# RoverPCB_version_4_2.net
KiCad netlist of a schematic drawn in EAGLE
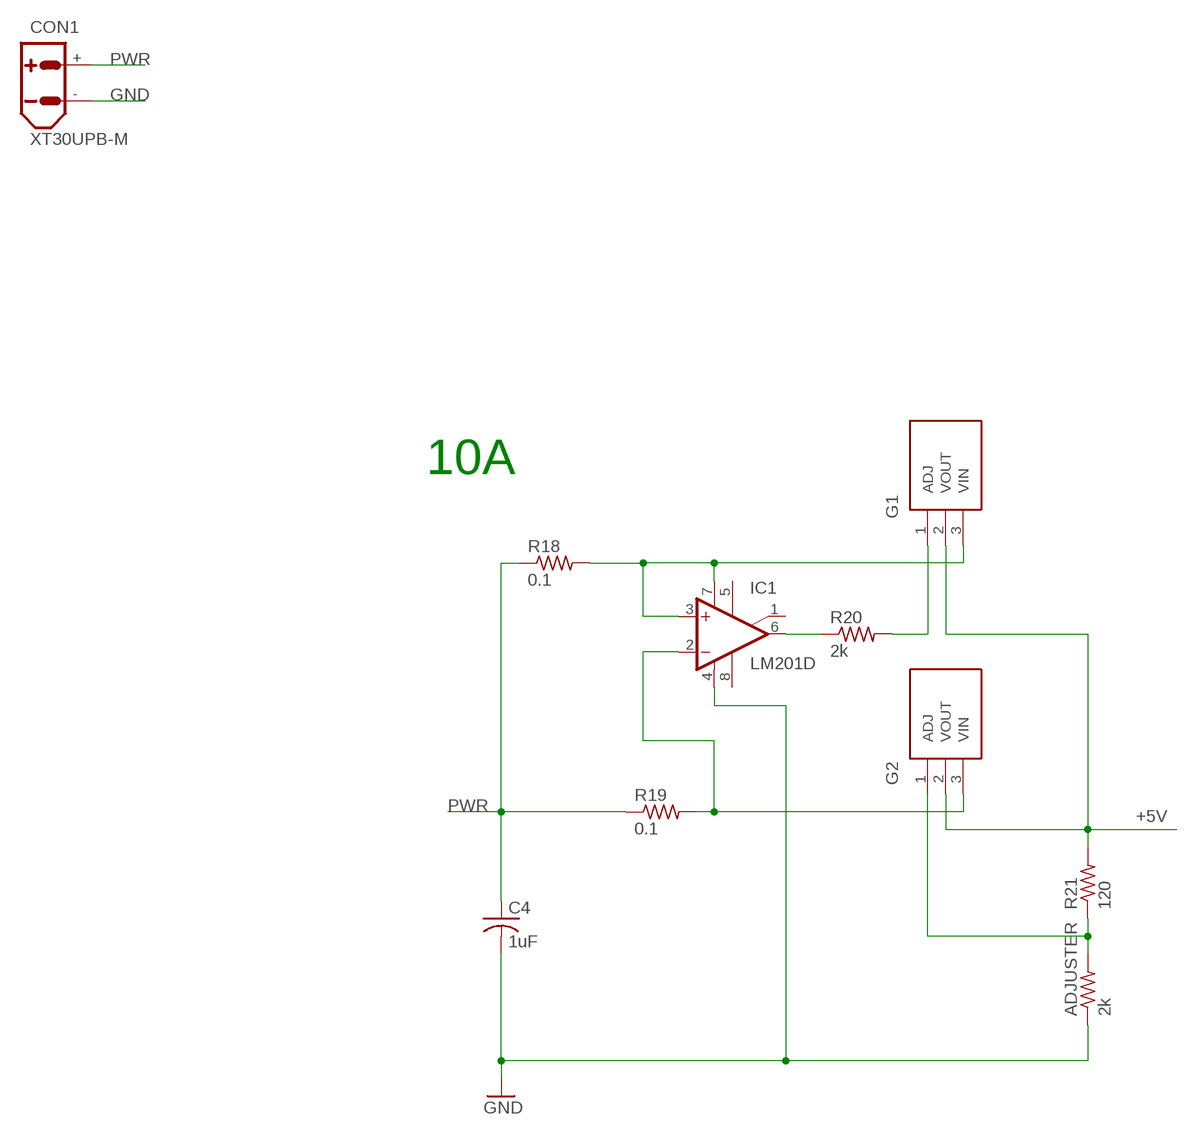
[diagram p0: schematic, sheet 1]
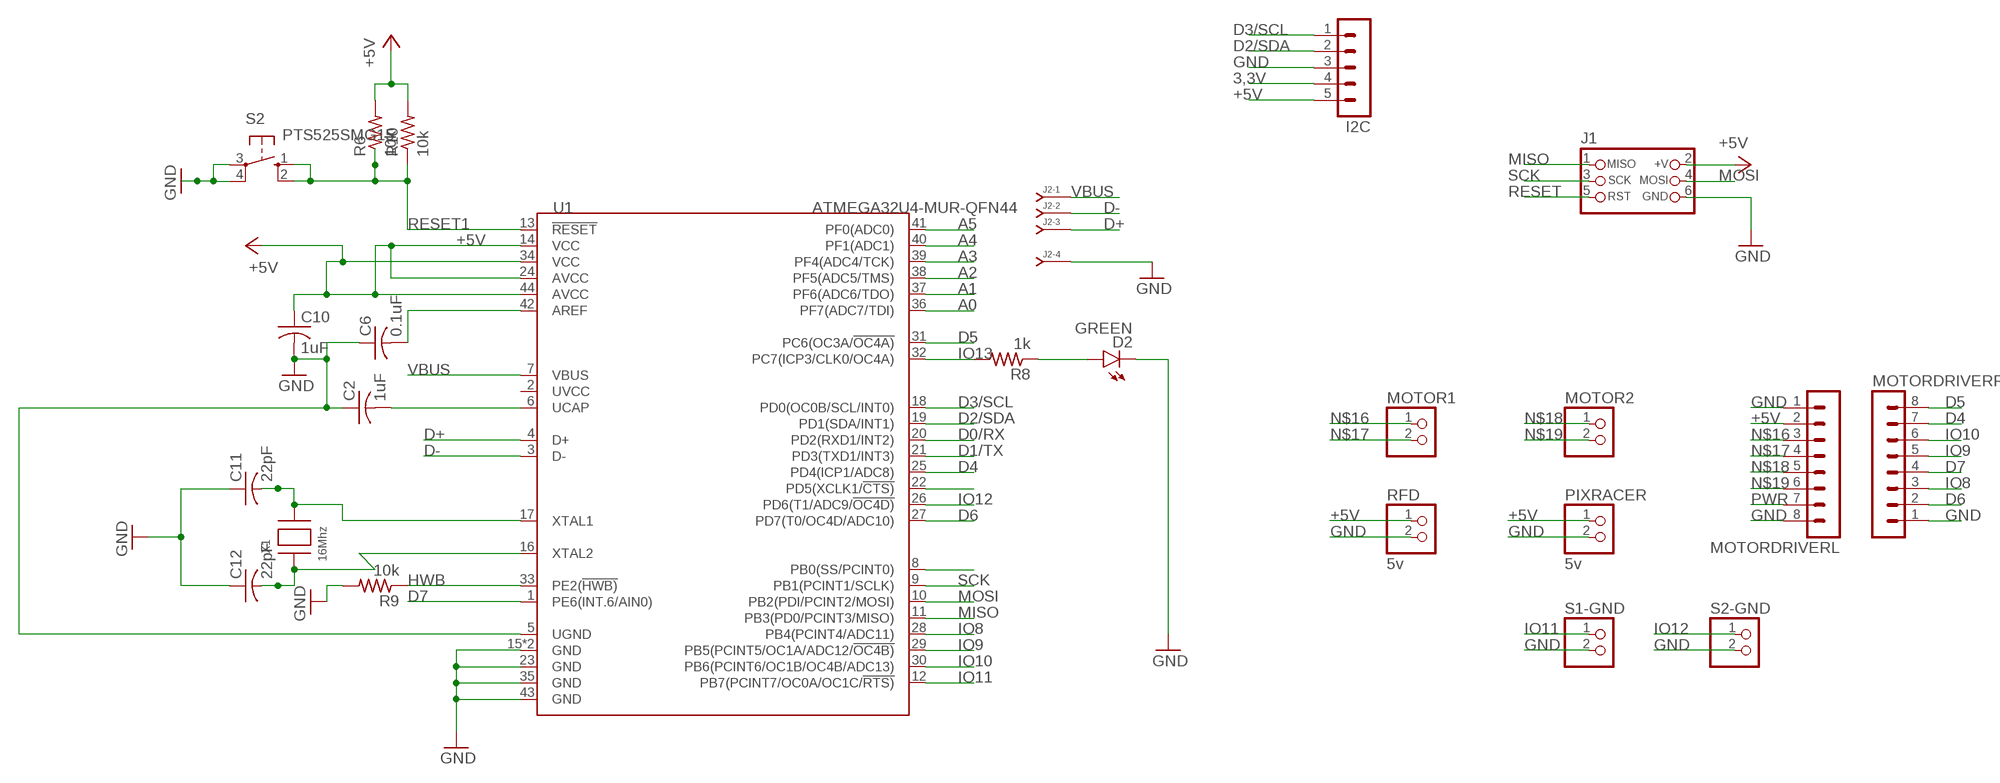
[diagram p1: schematic, sheet 2]

(export (version "E")
  (design (tool "Eeschema 10.0.6"))
  (components
    (comp (ref "ADJUSTER")
      (value "2k")
      (footprint "eagle-import:0204_5")
      (libsource (lib "eagle-import") (part "R-US_0204/5"))
    )
    (comp (ref "C4")
      (value "1uF")
      (footprint "eagle-import:C0402K")
      (libsource (lib "eagle-import") (part "C-USC0402K"))
    )
    (comp (ref "CON1")
      (value "XT30UPB-M")
      (footprint "eagle-import:XT30UPB-M")
      (libsource (lib "eagle-import") (part "XT30UPB-M"))
    )
    (comp (ref "IC1")
      (value "LM201D")
      (footprint "eagle-import:SO08")
      (libsource (lib "eagle-import") (part "LM201D"))
    )
    (comp (ref "IC11")
      (value "G1")
      (footprint "eagle-import:TO254P470X1028X1955-3P")
      (fields
        (field (name "ARROW_PART_NUMBER") "LM338T/NOPB")
        (field (name "MOUSER_PART_NUMBER") "926-LM338T/NOPB")
      )
      (libsource (lib "eagle-import") (part "LM338T_NOPB"))
    )
    (comp (ref "IC12")
      (value "G2")
      (footprint "eagle-import:TO254P470X1028X1955-3P")
      (fields
        (field (name "ARROW_PART_NUMBER") "LM338T/NOPB")
        (field (name "MOUSER_PART_NUMBER") "926-LM338T/NOPB")
      )
      (libsource (lib "eagle-import") (part "LM338T_NOPB"))
    )
    (comp (ref "R18")
      (value "0.1")
      (footprint "eagle-import:M1206")
      (libsource (lib "eagle-import") (part "R-US_M1206"))
    )
    (comp (ref "R19")
      (value "0.1")
      (footprint "eagle-import:M1206")
      (libsource (lib "eagle-import") (part "R-US_M1206"))
    )
    (comp (ref "R20")
      (value "2k")
      (footprint "eagle-import:R0805")
      (libsource (lib "eagle-import") (part "R-US_R0805"))
    )
    (comp (ref "R21")
      (value "120")
      (footprint "eagle-import:R0805")
      (libsource (lib "eagle-import") (part "R-US_R0805"))
    )
    (comp (ref "C2")
      (value "1uF")
      (footprint "eagle-import:C0805")
      (libsource (lib "eagle-import") (part "C-USC0805"))
    )
    (comp (ref "C6")
      (value "0.1uF")
      (footprint "eagle-import:C0805")
      (libsource (lib "eagle-import") (part "C-USC0805"))
    )
    (comp (ref "C10")
      (value "1uF")
      (footprint "eagle-import:C0805")
      (libsource (lib "eagle-import") (part "C-USC0805"))
    )
    (comp (ref "C11")
      (value "22pF")
      (footprint "eagle-import:C0805")
      (libsource (lib "eagle-import") (part "C-USC0805"))
    )
    (comp (ref "C12")
      (value "22pF")
      (footprint "eagle-import:C0805")
      (libsource (lib "eagle-import") (part "C-USC0805"))
    )
    (comp (ref "D2")
      (value "GREEN")
      (footprint "eagle-import:LED-0603")
      (libsource (lib "eagle-import") (part "LED-GREEN0603"))
    )
    (comp (ref "I2C")
      (value "MA05-1")
      (footprint "eagle-import:MA05-1")
      (libsource (lib "eagle-import") (part "MA05-1"))
    )
    (comp (ref "J1")
      (value "CON_HEADER_PRG_AVR_ICSP-PTH")
      (footprint "eagle-import:HEADER_PRG_2X03")
      (libsource (lib "eagle-import") (part "CON_HEADER_PRG_AVR_ICSP-PTH"))
    )
    (comp (ref "J2")
      (value "J-04-SIP-100")
      (footprint "eagle-import:SIP-100-04")
      (libsource (lib "eagle-import") (part "J-04-SIP-100"))
    )
    (comp (ref "MOTOR1")
      (value "PINHD-1X2")
      (footprint "eagle-import:1X02")
      (libsource (lib "eagle-import") (part "PINHD-1X2"))
    )
    (comp (ref "MOTOR2")
      (value "PINHD-1X2")
      (footprint "eagle-import:1X02")
      (libsource (lib "eagle-import") (part "PINHD-1X2"))
    )
    (comp (ref "MOTORDRIVERL")
      (value "MA08-1")
      (footprint "eagle-import:MA08-1")
      (libsource (lib "eagle-import") (part "MA08-1"))
    )
    (comp (ref "MOTORDRIVERR")
      (value "MA08-1")
      (footprint "eagle-import:MA08-1")
      (libsource (lib "eagle-import") (part "MA08-1"))
    )
    (comp (ref "PIXRACER")
      (value "5v")
      (footprint "eagle-import:1X02")
      (fields (field (name "SPICEPREFIX") "R"))
      (libsource (lib "eagle-import") (part "PINHD-1X2"))
    )
    (comp (ref "R6")
      (value "10k")
      (footprint "eagle-import:R0805")
      (libsource (lib "eagle-import") (part "R-US_R0805"))
    )
    (comp (ref "R8")
      (value "1k")
      (footprint "eagle-import:R0805")
      (fields (field (name "SPICEPREFIX") "R"))
      (libsource (lib "eagle-import") (part "R-US_R0805"))
    )
    (comp (ref "R9")
      (value "10k")
      (footprint "eagle-import:R0805")
      (fields (field (name "SPICEPREFIX") "R"))
      (libsource (lib "eagle-import") (part "R-US_R0805"))
    )
    (comp (ref "R10")
      (value "10k")
      (footprint "eagle-import:R0805")
      (libsource (lib "eagle-import") (part "R-US_R0805"))
    )
    (comp (ref "RFD")
      (value "5v")
      (footprint "eagle-import:1X02")
      (fields (field (name "SPICEPREFIX") "R"))
      (libsource (lib "eagle-import") (part "PINHD-1X2"))
    )
    (comp (ref "S1-GND")
      (value "PINHD-1X2")
      (footprint "eagle-import:1X02")
      (libsource (lib "eagle-import") (part "PINHD-1X2"))
    )
    (comp (ref "S2")
      (value "PTS525SMG15")
      (footprint "eagle-import:SMG15")
      (fields (field (name "MF") "C&K Components") (field (name "MPN") "PTS525SMG15SMTR2LFS"))
      (libsource (lib "eagle-import") (part "PTS525G15SM"))
    )
    (comp (ref "S2-GND")
      (value "PINHD-1X2")
      (footprint "eagle-import:1X02")
      (libsource (lib "eagle-import") (part "PINHD-1X2"))
    )
    (comp (ref "U1")
      (value "ATMEGA32U4-MUR-QFN44")
      (footprint "eagle-import:QFN44G-0.5-7X7MM")
      (fields (field (name "MPN") "ATMEGA32U4-MUR"))
      (libsource (lib "eagle-import") (part "MCU-ATMEGA32U4-MUR(VQFN44)"))
    )
    (comp (ref "X1")
      (value "16Mhz")
      (footprint "eagle-import:NX5032")
      (libsource (lib "eagle-import") (part "XTALNX5032"))
    )
  )
  (nets
    (net (code "1") (name "+5V") (class "Default")
      (node (ref "C10") (pin "1") (pinfunction "1_1") (pintype "passive"))
      (node (ref "I2C") (pin "5") (pinfunction "5_5") (pintype "passive"))
      (node (ref "IC11") (pin "2") (pinfunction "VOUT_2") (pintype "bidirectional"))
      (node (ref "IC12") (pin "2") (pinfunction "VOUT_2") (pintype "bidirectional"))
      (node (ref "J1") (pin "2") (pinfunction "+V_2") (pintype "passive"))
      (node (ref "MOTORDRIVERL") (pin "2") (pinfunction "2_2") (pintype "passive"))
      (node (ref "PIXRACER") (pin "1") (pinfunction "1_1") (pintype "passive"))
      (node (ref "R10") (pin "2") (pinfunction "2_2") (pintype "passive"))
      (node (ref "R21") (pin "2") (pinfunction "2_2") (pintype "passive"))
      (node (ref "R6") (pin "2") (pinfunction "2_2") (pintype "passive"))
      (node (ref "RFD") (pin "1") (pinfunction "1_1") (pintype "passive"))
      (node (ref "U1") (pin "14") (pinfunction "VCC_14") (pintype "bidirectional"))
      (node (ref "U1") (pin "24") (pinfunction "AVCC_24") (pintype "bidirectional"))
      (node (ref "U1") (pin "34") (pinfunction "VCC_34") (pintype "bidirectional"))
      (node (ref "U1") (pin "44") (pinfunction "AVCC_44") (pintype "bidirectional"))
    )
    (net (code "2") (name "3,3V") (class "Default")
      (node (ref "I2C") (pin "4") (pinfunction "4_4") (pintype "passive"))
    )
    (net (code "3") (name "A0") (class "Default")
      (node (ref "U1") (pin "36") (pinfunction "PF7(ADC7/TDI)_36") (pintype "bidirectional"))
    )
    (net (code "4") (name "A1") (class "Default")
      (node (ref "U1") (pin "37") (pinfunction "PF6(ADC6/TDO)_37") (pintype "bidirectional"))
    )
    (net (code "5") (name "A2") (class "Default")
      (node (ref "U1") (pin "38") (pinfunction "PF5(ADC5/TMS)_38") (pintype "bidirectional"))
    )
    (net (code "6") (name "A3") (class "Default")
      (node (ref "U1") (pin "39") (pinfunction "PF4(ADC4/TCK)_39") (pintype "bidirectional"))
    )
    (net (code "7") (name "A4") (class "Default")
      (node (ref "U1") (pin "40") (pinfunction "PF1(ADC1)_40") (pintype "bidirectional"))
    )
    (net (code "8") (name "A5") (class "Default")
      (node (ref "U1") (pin "41") (pinfunction "PF0(ADC0)_41") (pintype "bidirectional"))
    )
    (net (code "9") (name "D+") (class "Default")
      (node (ref "J2") (pin "3") (pinfunction "J_3") (pintype "passive"))
      (node (ref "U1") (pin "4") (pinfunction "D+_4") (pintype "bidirectional"))
    )
    (net (code "10") (name "D-") (class "Default")
      (node (ref "J2") (pin "2") (pinfunction "J_2") (pintype "passive"))
      (node (ref "U1") (pin "3") (pinfunction "D-_3") (pintype "bidirectional"))
    )
    (net (code "11") (name "D0{slash}RX") (class "Default")
      (node (ref "U1") (pin "20") (pinfunction "PD2(RXD1/INT2)_20") (pintype "bidirectional"))
    )
    (net (code "12") (name "D1{slash}TX") (class "Default")
      (node (ref "U1") (pin "21") (pinfunction "PD3(TXD1/INT3)_21") (pintype "bidirectional"))
    )
    (net (code "13") (name "D2{slash}SDA") (class "Default")
      (node (ref "I2C") (pin "2") (pinfunction "2_2") (pintype "passive"))
      (node (ref "U1") (pin "19") (pinfunction "PD1(SDA/INT1)_19") (pintype "bidirectional"))
    )
    (net (code "14") (name "D3{slash}SCL") (class "Default")
      (node (ref "I2C") (pin "1") (pinfunction "1_1") (pintype "passive"))
      (node (ref "U1") (pin "18") (pinfunction "PD0(OC0B/SCL/INT0)_18") (pintype "bidirectional"))
    )
    (net (code "15") (name "D4") (class "Default")
      (node (ref "MOTORDRIVERR") (pin "7") (pinfunction "7_7") (pintype "passive"))
      (node (ref "U1") (pin "25") (pinfunction "PD4(ICP1/ADC8)_25") (pintype "bidirectional"))
    )
    (net (code "16") (name "D5") (class "Default")
      (node (ref "MOTORDRIVERR") (pin "8") (pinfunction "8_8") (pintype "passive"))
      (node (ref "U1") (pin "31") (pinfunction "PC6(OC3A/~{OC4A})_31") (pintype "bidirectional"))
    )
    (net (code "17") (name "D6") (class "Default")
      (node (ref "MOTORDRIVERR") (pin "2") (pinfunction "2_2") (pintype "passive"))
      (node (ref "U1") (pin "27") (pinfunction "PD7(T0/OC4D/ADC10)_27") (pintype "bidirectional"))
    )
    (net (code "18") (name "D7") (class "Default")
      (node (ref "MOTORDRIVERR") (pin "4") (pinfunction "4_4") (pintype "passive"))
      (node (ref "U1") (pin "1") (pinfunction "PE6(INT.6/AIN0)_1") (pintype "bidirectional"))
    )
    (net (code "19") (name "GND") (class "Default")
      (node (ref "ADJUSTER") (pin "1") (pinfunction "1_1") (pintype "passive"))
      (node (ref "C10") (pin "2") (pinfunction "2_2") (pintype "passive"))
      (node (ref "C11") (pin "1") (pinfunction "1_1") (pintype "passive"))
      (node (ref "C12") (pin "1") (pinfunction "1_1") (pintype "passive"))
      (node (ref "C2") (pin "1") (pinfunction "1_1") (pintype "passive"))
      (node (ref "C4") (pin "2") (pinfunction "2_2") (pintype "passive"))
      (node (ref "C6") (pin "1") (pinfunction "1_1") (pintype "passive"))
      (node (ref "CON1") (pin "-") (pinfunction "-_-") (pintype "power_in"))
      (node (ref "D2") (pin "C") (pinfunction "C_C") (pintype "passive"))
      (node (ref "I2C") (pin "3") (pinfunction "3_3") (pintype "passive"))
      (node (ref "IC1") (pin "4") (pinfunction "V-_4") (pintype "power_in"))
      (node (ref "J1") (pin "6") (pinfunction "GND_6") (pintype "passive"))
      (node (ref "J2") (pin "4") (pinfunction "J_4") (pintype "passive"))
      (node (ref "MOTORDRIVERL") (pin "1") (pinfunction "1_1") (pintype "passive"))
      (node (ref "MOTORDRIVERL") (pin "8") (pinfunction "8_8") (pintype "passive"))
      (node (ref "MOTORDRIVERR") (pin "1") (pinfunction "1_1") (pintype "passive"))
      (node (ref "PIXRACER") (pin "2") (pinfunction "2_2") (pintype "passive"))
      (node (ref "R9") (pin "2") (pinfunction "2_2") (pintype "passive"))
      (node (ref "RFD") (pin "2") (pinfunction "2_2") (pintype "passive"))
      (node (ref "S1-GND") (pin "2") (pinfunction "2_2") (pintype "passive"))
      (node (ref "S2") (pin "3") (pinfunction "P_3") (pintype "passive"))
      (node (ref "S2") (pin "4") (pinfunction "P_4") (pintype "passive"))
      (node (ref "S2-GND") (pin "2") (pinfunction "2_2") (pintype "passive"))
      (node (ref "U1") (pin "15") (pinfunction "GND_15") (pintype "bidirectional"))
      (node (ref "U1") (pin "23") (pinfunction "GND_23") (pintype "bidirectional"))
      (node (ref "U1") (pin "35") (pinfunction "GND_35") (pintype "bidirectional"))
      (node (ref "U1") (pin "43") (pinfunction "GND_43") (pintype "bidirectional"))
      (node (ref "U1") (pin "5") (pinfunction "UGND_5") (pintype "bidirectional"))
      (node (ref "U1") (pin "TAB") (pinfunction "GND_TAB") (pintype "bidirectional"))
    )
    (net (code "20") (name "HWB") (class "Default")
      (node (ref "R9") (pin "1") (pinfunction "1_1") (pintype "passive"))
      (node (ref "U1") (pin "33") (pinfunction "PE2(~{HWB})_33") (pintype "bidirectional"))
    )
    (net (code "21") (name "IO8") (class "Default")
      (node (ref "MOTORDRIVERR") (pin "3") (pinfunction "3_3") (pintype "passive"))
      (node (ref "U1") (pin "28") (pinfunction "PB4(PCINT4/ADC11)_28") (pintype "bidirectional"))
    )
    (net (code "22") (name "IO9") (class "Default")
      (node (ref "MOTORDRIVERR") (pin "5") (pinfunction "5_5") (pintype "passive"))
      (node (ref "U1") (pin "29") (pinfunction "PB5(PCINT5/OC1A/ADC12/~{OC4B})_29") (pintype "bidirectional"))
    )
    (net (code "23") (name "IO10") (class "Default")
      (node (ref "MOTORDRIVERR") (pin "6") (pinfunction "6_6") (pintype "passive"))
      (node (ref "U1") (pin "30") (pinfunction "PB6(PCINT6/OC1B/OC4B/ADC13)_30") (pintype "bidirectional"))
    )
    (net (code "24") (name "IO11") (class "Default")
      (node (ref "S1-GND") (pin "1") (pinfunction "1_1") (pintype "passive"))
      (node (ref "U1") (pin "12") (pinfunction "PB7(PCINT7/OC0A/OC1C/~{RTS})_12") (pintype "bidirectional"))
    )
    (net (code "25") (name "IO12") (class "Default")
      (node (ref "S2-GND") (pin "1") (pinfunction "1_1") (pintype "passive"))
      (node (ref "U1") (pin "26") (pinfunction "PD6(T1/ADC9/~{OC4D})_26") (pintype "bidirectional"))
    )
    (net (code "26") (name "IO13") (class "Default")
      (node (ref "R8") (pin "2") (pinfunction "2_2") (pintype "passive"))
      (node (ref "U1") (pin "32") (pinfunction "PC7(ICP3/CLK0/OC4A)_32") (pintype "bidirectional"))
    )
    (net (code "27") (name "MISO") (class "Default")
      (node (ref "J1") (pin "1") (pinfunction "MISO_1") (pintype "passive"))
      (node (ref "U1") (pin "11") (pinfunction "PB3(PD0/PCINT3/MISO)_11") (pintype "bidirectional"))
    )
    (net (code "28") (name "MOSI") (class "Default")
      (node (ref "J1") (pin "4") (pinfunction "MOSI_4") (pintype "passive"))
      (node (ref "U1") (pin "10") (pinfunction "PB2(PDI/PCINT2/MOSI)_10") (pintype "bidirectional"))
    )
    (net (code "29") (name "N$16") (class "Default")
      (node (ref "MOTOR1") (pin "1") (pinfunction "1_1") (pintype "passive"))
      (node (ref "MOTORDRIVERL") (pin "3") (pinfunction "3_3") (pintype "passive"))
    )
    (net (code "30") (name "N$17") (class "Default")
      (node (ref "MOTOR1") (pin "2") (pinfunction "2_2") (pintype "passive"))
      (node (ref "MOTORDRIVERL") (pin "4") (pinfunction "4_4") (pintype "passive"))
    )
    (net (code "31") (name "N$18") (class "Default")
      (node (ref "MOTOR2") (pin "1") (pinfunction "1_1") (pintype "passive"))
      (node (ref "MOTORDRIVERL") (pin "5") (pinfunction "5_5") (pintype "passive"))
    )
    (net (code "32") (name "N$19") (class "Default")
      (node (ref "MOTOR2") (pin "2") (pinfunction "2_2") (pintype "passive"))
      (node (ref "MOTORDRIVERL") (pin "6") (pinfunction "6_6") (pintype "passive"))
    )
    (net (code "33") (name "Net-(D2-PadA)") (class "Default")
      (node (ref "D2") (pin "A") (pinfunction "A_A") (pintype "passive"))
      (node (ref "R8") (pin "1") (pinfunction "1_1") (pintype "passive"))
    )
    (net (code "34") (name "Net-(IC1-+IN)") (class "Default")
      (node (ref "IC1") (pin "3") (pinfunction "+IN_3") (pintype "input"))
      (node (ref "IC1") (pin "7") (pinfunction "V+_7") (pintype "power_in"))
      (node (ref "IC11") (pin "3") (pinfunction "VIN_3") (pintype "bidirectional"))
      (node (ref "R18") (pin "2") (pinfunction "2_2") (pintype "passive"))
    )
    (net (code "35") (name "Net-(IC1--IN)") (class "Default")
      (node (ref "IC1") (pin "2") (pinfunction "-IN_2") (pintype "input"))
      (node (ref "IC12") (pin "3") (pinfunction "VIN_3") (pintype "bidirectional"))
      (node (ref "R19") (pin "2") (pinfunction "2_2") (pintype "passive"))
    )
    (net (code "36") (name "Net-(IC1-OUT)") (class "Default")
      (node (ref "IC1") (pin "6") (pinfunction "OUT_6") (pintype "output"))
      (node (ref "R20") (pin "1") (pinfunction "1_1") (pintype "passive"))
    )
    (net (code "37") (name "Net-(IC11-ADJ)") (class "Default")
      (node (ref "IC11") (pin "1") (pinfunction "ADJ_1") (pintype "bidirectional"))
      (node (ref "R20") (pin "2") (pinfunction "2_2") (pintype "passive"))
    )
    (net (code "38") (name "Net-(IC12-ADJ)") (class "Default")
      (node (ref "ADJUSTER") (pin "2") (pinfunction "2_2") (pintype "passive"))
      (node (ref "IC12") (pin "1") (pinfunction "ADJ_1") (pintype "bidirectional"))
      (node (ref "R21") (pin "1") (pinfunction "1_1") (pintype "passive"))
    )
    (net (code "39") (name "Net-(U1-AREF)") (class "Default")
      (node (ref "C6") (pin "2") (pinfunction "2_2") (pintype "passive"))
      (node (ref "U1") (pin "42") (pinfunction "AREF_42") (pintype "bidirectional"))
    )
    (net (code "40") (name "Net-(U1-UCAP)") (class "Default")
      (node (ref "C2") (pin "2") (pinfunction "2_2") (pintype "passive"))
      (node (ref "U1") (pin "6") (pinfunction "UCAP_6") (pintype "bidirectional"))
    )
    (net (code "41") (name "Net-(U1-XTAL1)") (class "Default")
      (node (ref "C11") (pin "2") (pinfunction "2_2") (pintype "passive"))
      (node (ref "U1") (pin "17") (pinfunction "XTAL1_17") (pintype "bidirectional"))
      (node (ref "X1") (pin "P$2") (pinfunction "P$2_P$2") (pintype "bidirectional"))
    )
    (net (code "42") (name "Net-(U1-XTAL2)") (class "Default")
      (node (ref "C12") (pin "2") (pinfunction "2_2") (pintype "passive"))
      (node (ref "U1") (pin "16") (pinfunction "XTAL2_16") (pintype "bidirectional"))
      (node (ref "X1") (pin "P$1") (pinfunction "P$1_P$1") (pintype "bidirectional"))
    )
    (net (code "43") (name "PWR") (class "Default")
      (node (ref "C4") (pin "1") (pinfunction "1_1") (pintype "passive"))
      (node (ref "CON1") (pin "+") (pinfunction "+_+") (pintype "power_in"))
      (node (ref "MOTORDRIVERL") (pin "7") (pinfunction "7_7") (pintype "passive"))
      (node (ref "R18") (pin "1") (pinfunction "1_1") (pintype "passive"))
      (node (ref "R19") (pin "1") (pinfunction "1_1") (pintype "passive"))
    )
    (net (code "44") (name "RESET") (class "Default")
      (node (ref "J1") (pin "5") (pinfunction "RST_5") (pintype "passive"))
    )
    (net (code "45") (name "RESET1") (class "Default")
      (node (ref "R10") (pin "1") (pinfunction "1_1") (pintype "passive"))
      (node (ref "R6") (pin "1") (pinfunction "1_1") (pintype "passive"))
      (node (ref "S2") (pin "1") (pinfunction "S_1") (pintype "passive"))
      (node (ref "S2") (pin "2") (pinfunction "S_2") (pintype "passive"))
      (node (ref "U1") (pin "13") (pinfunction "~{RESET}_13") (pintype "bidirectional"))
    )
    (net (code "46") (name "SCK") (class "Default")
      (node (ref "J1") (pin "3") (pinfunction "SCK_3") (pintype "passive"))
      (node (ref "U1") (pin "9") (pinfunction "PB1(PCINT1/SCLK)_9") (pintype "bidirectional"))
    )
    (net (code "47") (name "VBUS") (class "Default")
      (node (ref "J2") (pin "1") (pinfunction "J_1") (pintype "passive"))
      (node (ref "U1") (pin "7") (pinfunction "VBUS_7") (pintype "bidirectional"))
    )
    (net (code "48") (name "unconnected-(IC1-CMP-Pad8)") (class "Default")
      (node (ref "IC1") (pin "8") (pinfunction "CMP_8") (pintype "passive"))
    )
    (net (code "49") (name "unconnected-(IC1-ON-Pad5)") (class "Default")
      (node (ref "IC1") (pin "5") (pinfunction "ON_5") (pintype "passive"))
    )
    (net (code "50") (name "unconnected-(IC1-ON{slash}CMP-Pad1)") (class "Default")
      (node (ref "IC1") (pin "1") (pinfunction "ON/CMP_1") (pintype "passive"))
    )
    (net (code "51") (name "unconnected-(U1-PB0(SS{slash}PCINT0)-Pad8)") (class "Default")
      (node (ref "U1") (pin "8") (pinfunction "PB0(SS/PCINT0)_8") (pintype "bidirectional"))
    )
    (net (code "52") (name "unconnected-(U1-PD5(XCLK1{slash}~{CTS})-Pad22)") (class "Default")
      (node (ref "U1") (pin "22") (pinfunction "PD5(XCLK1/~{CTS})_22") (pintype "bidirectional"))
    )
    (net (code "53") (name "unconnected-(U1-UVCC-Pad2)") (class "Default")
      (node (ref "U1") (pin "2") (pinfunction "UVCC_2") (pintype "bidirectional"))
    )
  )
)
